# AlienWhoopRx.net
KiCad netlist of a schematic drawn in EAGLE
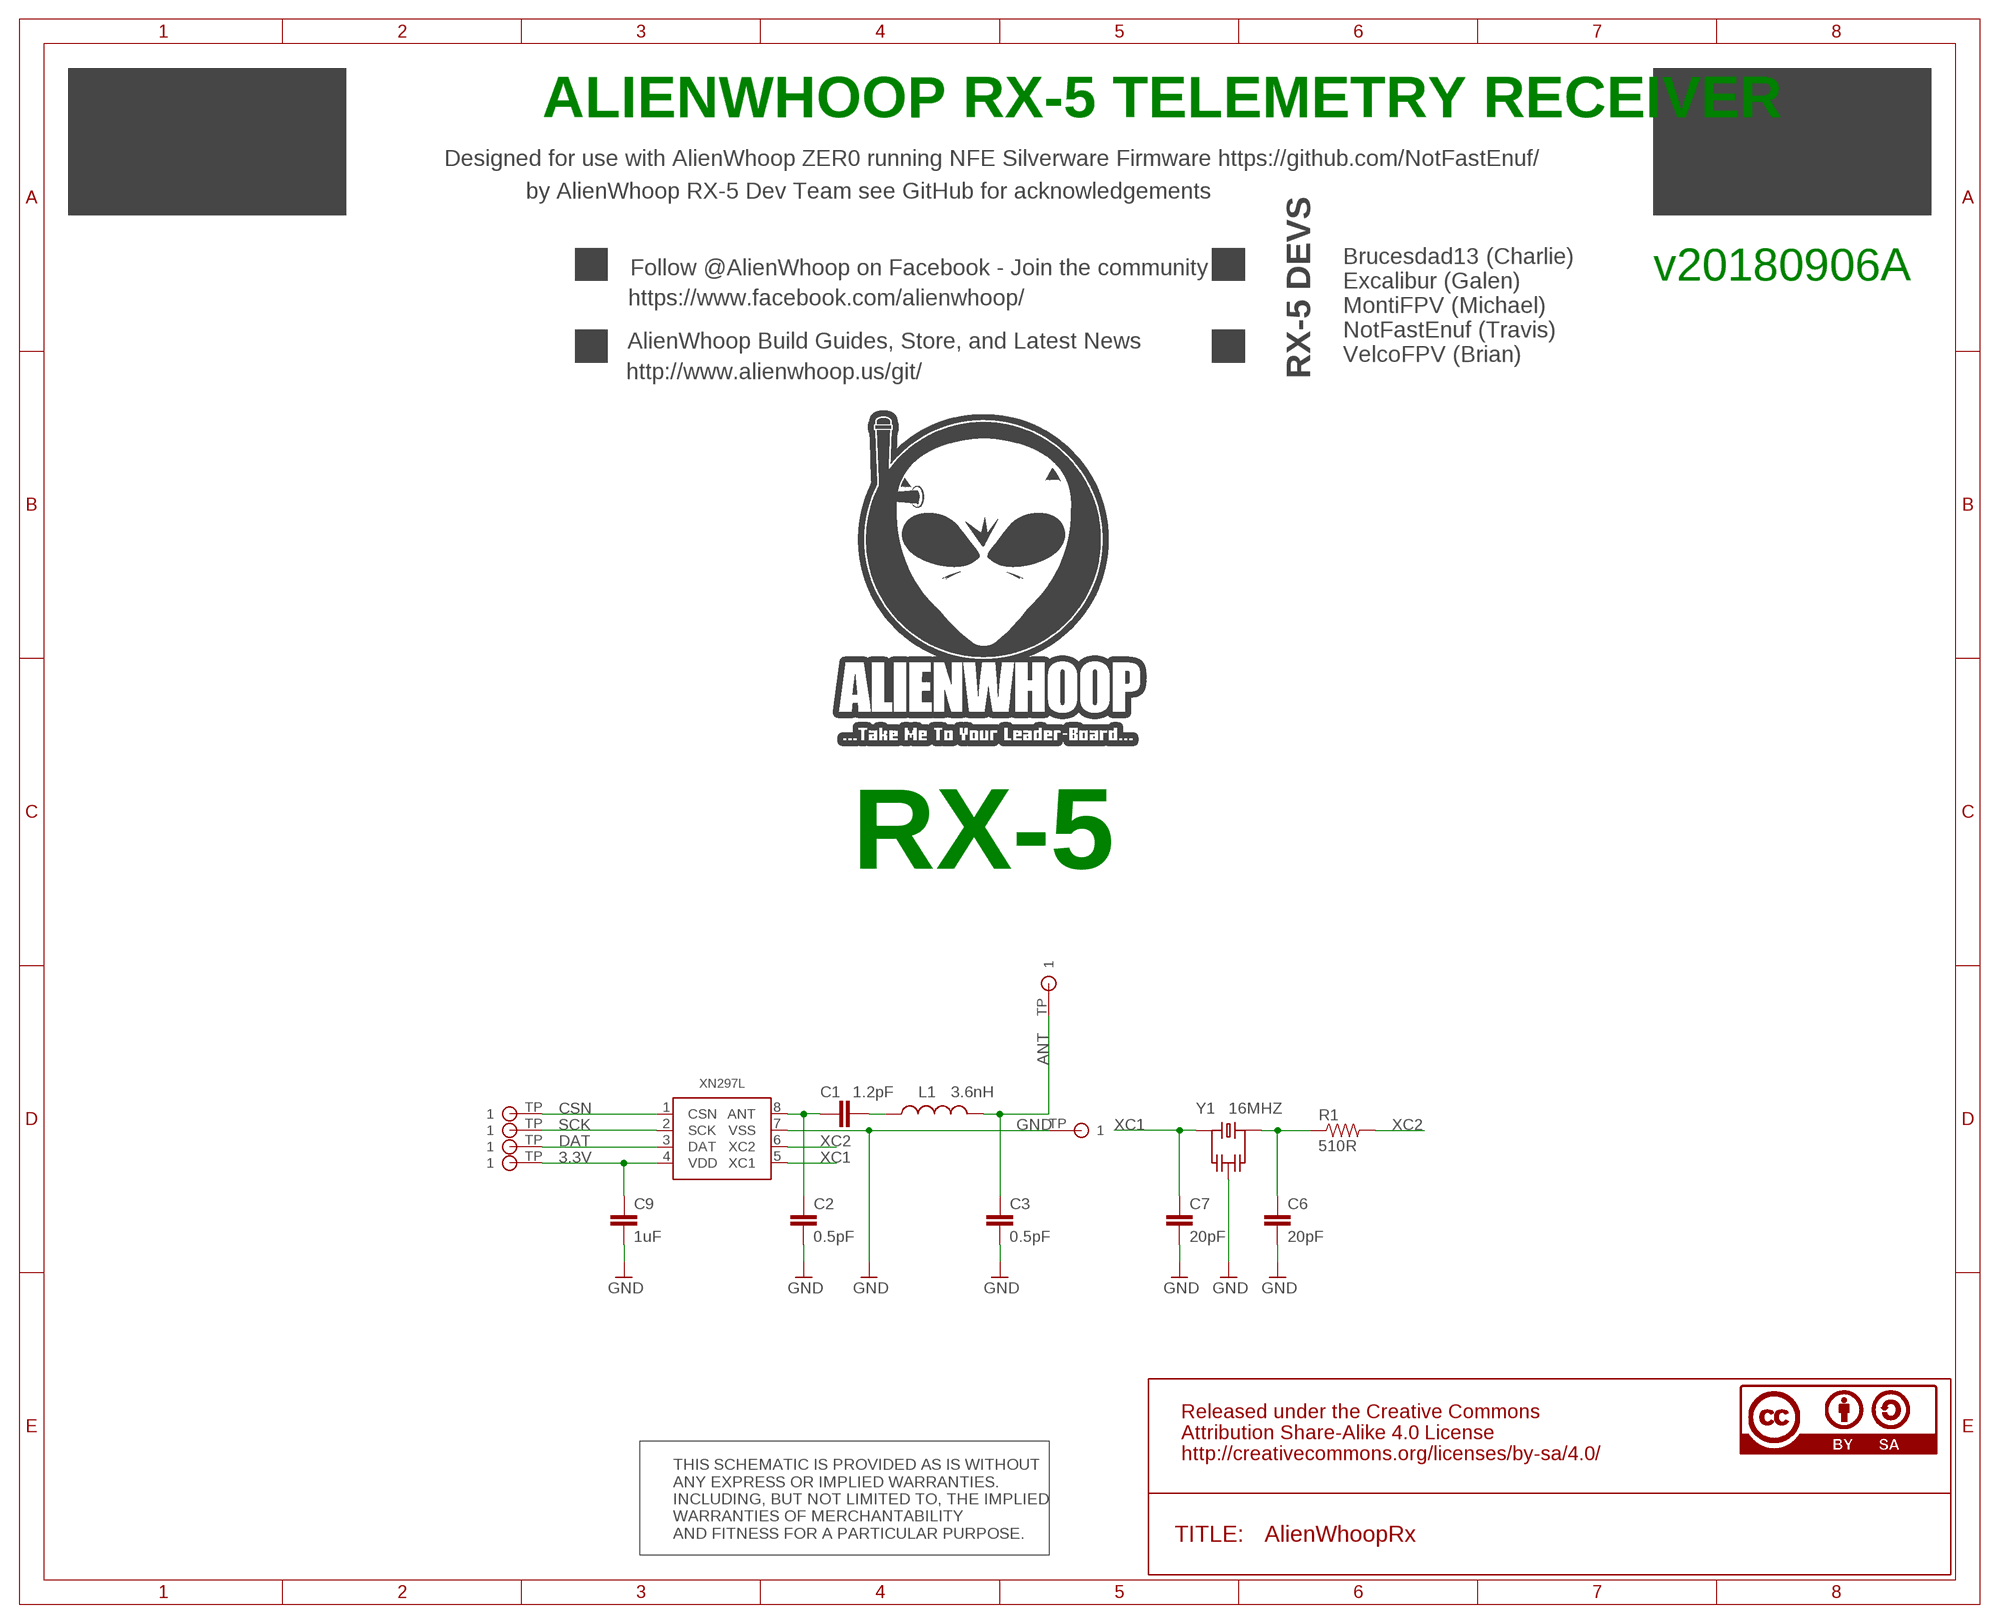
[diagram p0: schematic, sheet 1]

(export (version "E")
  (design (tool "Eeschema 10.0.6"))
  (components
    (comp (ref "3.3V2")
      (value "TESTPAD")
      (footprint "eagle-import:TESTPAD")
      (libsource (lib "eagle-import") (part "TESTPAD"))
    )
    (comp (ref "C1")
      (value "1.2pF")
      (footprint "eagle-import:0402")
      (fields (field (name "PARTNO") "0402YA1R2CAT2A"))
      (libsource (lib "eagle-import") (part "CAP_0402"))
    )
    (comp (ref "C2")
      (value "0.5pF")
      (footprint "eagle-import:0402")
      (fields (field (name "PARTNO") "VJ0402A0R5BXJCW1BC"))
      (libsource (lib "eagle-import") (part "CAP_0402"))
    )
    (comp (ref "C3")
      (value "0.5pF")
      (footprint "eagle-import:0402")
      (fields (field (name "PARTNO") "VJ0402A0R5BXJCW1BC"))
      (libsource (lib "eagle-import") (part "CAP_0402"))
    )
    (comp (ref "C6")
      (value "20pF")
      (footprint "eagle-import:0402")
      (fields (field (name "PARTNO") "GJM1555C1H200FB01D"))
      (libsource (lib "eagle-import") (part "CAP_0402"))
    )
    (comp (ref "C7")
      (value "20pF")
      (footprint "eagle-import:0402")
      (fields (field (name "PARTNO") "GJM1555C1H200FB01D"))
      (libsource (lib "eagle-import") (part "CAP_0402"))
    )
    (comp (ref "C9")
      (value "1uF")
      (footprint "eagle-import:0402")
      (fields (field (name "PARTNO") "GRM155C71A105KE11D"))
      (libsource (lib "eagle-import") (part "CAP_0402"))
    )
    (comp (ref "GND23")
      (value "TESTPAD")
      (footprint "eagle-import:TESTPAD")
      (libsource (lib "eagle-import") (part "TESTPAD"))
    )
    (comp (ref "L1")
      (value "3.6nH")
      (footprint "eagle-import:0402")
      (fields (field (name "PARTNO") "MHQ1005P3N6ST000"))
      (libsource (lib "eagle-import") (part "MHQ1005P3.6NH"))
    )
    (comp (ref "R1")
      (value "510R")
      (footprint "eagle-import:0402")
      (fields (field (name "PARTNO") "CR0402-FX-5100GLF"))
      (libsource (lib "eagle-import") (part "RES_0402"))
    )
    (comp (ref "SPI_CS")
      (value "TESTPAD")
      (footprint "eagle-import:TESTPAD")
      (libsource (lib "eagle-import") (part "TESTPAD"))
    )
    (comp (ref "U$6")
      (value "TESTPAD")
      (footprint "eagle-import:TESTPAD")
      (libsource (lib "eagle-import") (part "TESTPAD"))
    )
    (comp (ref "U$13")
      (value "TESTPAD")
      (footprint "eagle-import:TESTPAD")
      (libsource (lib "eagle-import") (part "TESTPAD"))
    )
    (comp (ref "U$14")
      (value "TESTPAD")
      (footprint "eagle-import:TESTPAD")
      (libsource (lib "eagle-import") (part "TESTPAD"))
    )
    (comp (ref "U1")
      (value "XN297L")
      (footprint "eagle-import:SOP8L")
      (fields (field (name "PARTNO") "XN297LBW"))
      (libsource (lib "eagle-import") (part "XN297L"))
    )
    (comp (ref "Y1")
      (value "16MHZ")
      (footprint "eagle-import:ECS-160-20-33-CKM-TR")
      (fields (field (name "PARTNO") "ECS-160-20-33-CKM-TR"))
      (libsource (lib "eagle-import") (part "ECS-160-20-33-CKM-TR16MHZ"))
    )
  )
  (nets
    (net (code "1") (name "/3.3V") (class "Default")
      (node (ref "3.3V2") (pin "TP") (pinfunction "1_TP") (pintype "bidirectional"))
      (node (ref "C9") (pin "1") (pinfunction "1_1") (pintype "passive"))
      (node (ref "U1") (pin "4") (pinfunction "VDD_4") (pintype "power_in"))
    )
    (net (code "2") (name "/ANT") (class "Default")
      (node (ref "C3") (pin "1") (pinfunction "1_1") (pintype "passive"))
      (node (ref "L1") (pin "2") (pinfunction "2_2") (pintype "passive"))
      (node (ref "U$6") (pin "TP") (pinfunction "1_TP") (pintype "bidirectional"))
    )
    (net (code "3") (name "/CSN") (class "Default")
      (node (ref "SPI_CS") (pin "TP") (pinfunction "1_TP") (pintype "bidirectional"))
      (node (ref "U1") (pin "1") (pinfunction "CSN_1") (pintype "bidirectional"))
    )
    (net (code "4") (name "/DAT") (class "Default")
      (node (ref "U$14") (pin "TP") (pinfunction "1_TP") (pintype "bidirectional"))
      (node (ref "U1") (pin "3") (pinfunction "DAT_3") (pintype "bidirectional"))
    )
    (net (code "5") (name "/SCK") (class "Default")
      (node (ref "U$13") (pin "TP") (pinfunction "1_TP") (pintype "bidirectional"))
      (node (ref "U1") (pin "2") (pinfunction "SCK_2") (pintype "bidirectional"))
    )
    (net (code "6") (name "/XC1") (class "Default")
      (node (ref "C7") (pin "1") (pinfunction "1_1") (pintype "passive"))
      (node (ref "U1") (pin "5") (pinfunction "XC1_5") (pintype "bidirectional"))
      (node (ref "Y1") (pin "1") (pinfunction "1_1") (pintype "passive"))
    )
    (net (code "7") (name "/XC2") (class "Default")
      (node (ref "R1") (pin "2") (pinfunction "2_2") (pintype "passive"))
      (node (ref "U1") (pin "6") (pinfunction "XC2_6") (pintype "bidirectional"))
    )
    (net (code "8") (name "GND") (class "Default")
      (node (ref "C2") (pin "2") (pinfunction "2_2") (pintype "passive"))
      (node (ref "C3") (pin "2") (pinfunction "2_2") (pintype "passive"))
      (node (ref "C6") (pin "2") (pinfunction "2_2") (pintype "passive"))
      (node (ref "C7") (pin "2") (pinfunction "2_2") (pintype "passive"))
      (node (ref "C9") (pin "2") (pinfunction "2_2") (pintype "passive"))
      (node (ref "GND23") (pin "TP") (pinfunction "1_TP") (pintype "bidirectional"))
      (node (ref "U1") (pin "7") (pinfunction "VSS_7") (pintype "power_in"))
      (node (ref "Y1") (pin "2") (pinfunction "2_2") (pintype "passive"))
      (node (ref "Y1") (pin "4") (pinfunction "2_4") (pintype "passive"))
    )
    (net (code "9") (name "Net-(C1-Pad2)") (class "Default")
      (node (ref "C1") (pin "2") (pinfunction "2_2") (pintype "passive"))
      (node (ref "L1") (pin "1") (pinfunction "1_1") (pintype "passive"))
    )
    (net (code "10") (name "Net-(C6-Pad1)") (class "Default")
      (node (ref "C6") (pin "1") (pinfunction "1_1") (pintype "passive"))
      (node (ref "R1") (pin "1") (pinfunction "1_1") (pintype "passive"))
      (node (ref "Y1") (pin "3") (pinfunction "3_3") (pintype "passive"))
    )
    (net (code "11") (name "Net-(U1-ANT)") (class "Default")
      (node (ref "C1") (pin "1") (pinfunction "1_1") (pintype "passive"))
      (node (ref "C2") (pin "1") (pinfunction "1_1") (pintype "passive"))
      (node (ref "U1") (pin "8") (pinfunction "ANT_8") (pintype "bidirectional"))
    )
  )
)
